# BarrelJack.net
KiCad netlist of a schematic drawn in Altium Designer
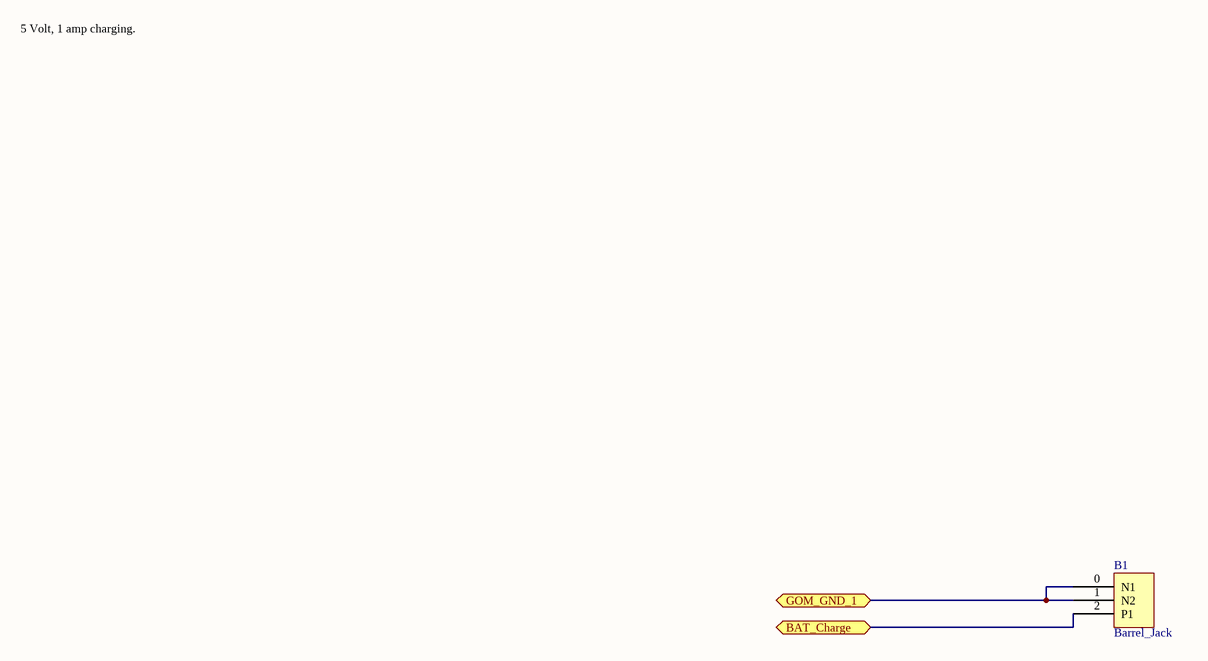
[diagram p0: BarrelJack.SchDoc]

(export (version "E")
  (design (tool "Eeschema 10.0.6"))
  (components
    (comp (ref "B1")
      (value "Barrel_Jack")
      (footprint "UmbilicalConnectors:Barrel_Jack")
      (libsource (lib "UmbilicalBoardV2") (part "Barrel_Jack"))
    )
  )
  (nets
    (net (code "1") (name "/BAT_Charge") (class "Default")
      (node (ref "B1") (pin "2") (pinfunction "P1_2") (pintype "passive"))
    )
    (net (code "2") (name "/GOM_GND_1") (class "Default")
      (node (ref "B1") (pin "0") (pinfunction "N1_0") (pintype "passive"))
      (node (ref "B1") (pin "1") (pinfunction "N2_1") (pintype "passive"))
    )
  )
)
